# BlueTooth.net
KiCad netlist of a schematic drawn in Altium Designer
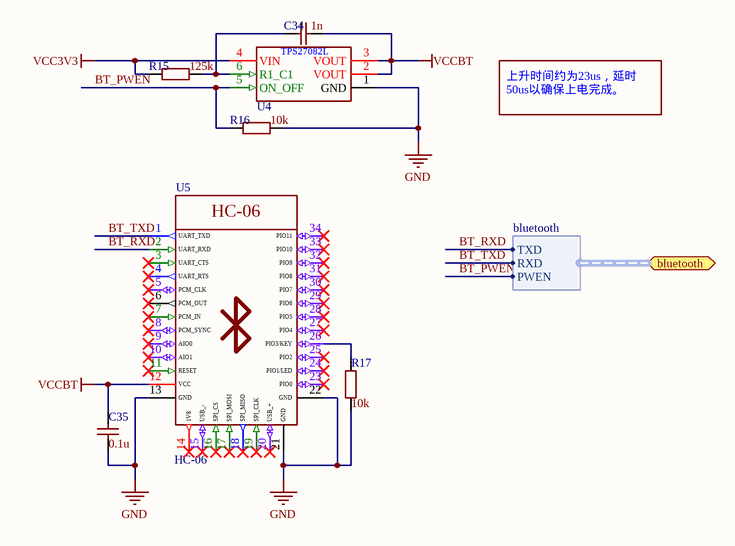
[diagram p0: BlueTooth.SchDoc]

(export (version "E")
  (design (tool "Eeschema 10.0.6"))
  (components
    (comp (ref "C34")
      (value "1n")
      (footprint "C0402_h")
      (description "Capacitor")
      (fields (field (name "PUBLISHER") "Altium Limited"))
      (libsource (lib "电子元件封装库") (part "贴片电容-无极性"))
    )
    (comp (ref "C35")
      (value "0.1u")
      (footprint "C0402_h")
      (description "Capacitor")
      (fields (field (name "PUBLISHER") "Altium Limited"))
      (libsource (lib "电子元件封装库") (part "贴片电容-无极性"))
    )
    (comp (ref "R15")
      (value "125k")
      (footprint "R0402")
      (description "Register")
      (libsource (lib "") (part "贴片电阻_1"))
    )
    (comp (ref "R16")
      (value "10k")
      (footprint "R0402")
      (description "Register")
      (libsource (lib "") (part "贴片电阻_1"))
    )
    (comp (ref "R17")
      (value "10k")
      (footprint "R0402")
      (description "Register")
      (libsource (lib "电子元件封装库") (part "贴片电阻"))
    )
    (comp (ref "U4")
      (value "TPS27082L")
      (footprint "SOT23-6")
      (description "load switch")
      (fields (field (name "PARTNUMBER") "TPS27082LDDC") (field (name "MANUFACTURER") "Texas Instruments"))
      (libsource (lib "电子元件封装库") (part "TPS27082LDDCR"))
    )
    (comp (ref "U5")
      (value "HC-06")
      (footprint "HC-0X-bluetooth")
      (description "HC-06 Bluetooth")
      (libsource (lib "电子元件封装库") (part "HC-06 Bluetooth"))
    )
  )
  (nets
    (net (code "2") (name "/BT_PWEN") (class "Default")
      (node (ref "R16") (pin "1") (pinfunction "1_1") (pintype "passive"))
      (node (ref "U4") (pin "5") (pinfunction "ON_OFF_5") (pintype "input"))
    )
    (net (code "3") (name "/BT_RXD") (class "Default")
      (node (ref "U5") (pin "2") (pinfunction "UART_RXD_2") (pintype "input"))
    )
    (net (code "4") (name "/BT_TXD") (class "Default")
      (node (ref "U5") (pin "1") (pinfunction "UART_TXD_1") (pintype "output"))
    )
    (net (code "6") (name "GND") (class "Default")
      (node (ref "C35") (pin "1") (pinfunction "1_1") (pintype "passive"))
      (node (ref "R16") (pin "2") (pinfunction "2_2") (pintype "passive"))
      (node (ref "R17") (pin "1") (pinfunction "1_1") (pintype "passive"))
      (node (ref "U4") (pin "1") (pinfunction "GND_1") (pintype "power_in"))
      (node (ref "U5") (pin "13") (pinfunction "GND_13") (pintype "power_in"))
      (node (ref "U5") (pin "21") (pinfunction "GND_21") (pintype "power_in"))
      (node (ref "U5") (pin "22") (pinfunction "GND_22") (pintype "power_in"))
    )
    (net (code "7") (name "Net-(U4-R1_C1)") (class "Default")
      (node (ref "C34") (pin "1") (pinfunction "1_1") (pintype "passive"))
      (node (ref "R15") (pin "2") (pinfunction "2_2") (pintype "passive"))
      (node (ref "U4") (pin "6") (pinfunction "R1_C1_6") (pintype "input"))
    )
    (net (code "8") (name "Net-(U5-PIO3{slash}KEY)") (class "Default")
      (node (ref "R17") (pin "2") (pinfunction "2_2") (pintype "passive"))
      (node (ref "U5") (pin "26") (pinfunction "PIO3/KEY_26") (pintype "bidirectional"))
    )
    (net (code "9") (name "VCC3V3") (class "Default")
      (node (ref "R15") (pin "1") (pinfunction "1_1") (pintype "passive"))
      (node (ref "U4") (pin "4") (pinfunction "VIN_4") (pintype "power_in"))
    )
    (net (code "10") (name "VCCBT") (class "Default")
      (node (ref "C34") (pin "2") (pinfunction "2_2") (pintype "passive"))
      (node (ref "C35") (pin "2") (pinfunction "2_2") (pintype "passive"))
      (node (ref "U4") (pin "2") (pinfunction "VOUT_2") (pintype "power_in"))
      (node (ref "U4") (pin "3") (pinfunction "VOUT_3") (pintype "power_in"))
      (node (ref "U5") (pin "12") (pinfunction "VCC_12") (pintype "power_in"))
    )
    (net (code "11") (name "unconnected-(U5-1V8-Pad14)") (class "Default")
      (node (ref "U5") (pin "14") (pinfunction "1V8_14") (pintype "output+no_connect"))
    )
    (net (code "12") (name "unconnected-(U5-AIO0-Pad9)") (class "Default")
      (node (ref "U5") (pin "9") (pinfunction "AIO0_9") (pintype "bidirectional+no_connect"))
    )
    (net (code "13") (name "unconnected-(U5-AIO1-Pad10)") (class "Default")
      (node (ref "U5") (pin "10") (pinfunction "AIO1_10") (pintype "bidirectional+no_connect"))
    )
    (net (code "14") (name "unconnected-(U5-PCM_CLK-Pad5)") (class "Default")
      (node (ref "U5") (pin "5") (pinfunction "PCM_CLK_5") (pintype "bidirectional+no_connect"))
    )
    (net (code "15") (name "unconnected-(U5-PCM_IN-Pad7)") (class "Default")
      (node (ref "U5") (pin "7") (pinfunction "PCM_IN_7") (pintype "input+no_connect"))
    )
    (net (code "16") (name "unconnected-(U5-PCM_OUT-Pad6)") (class "Default")
      (node (ref "U5") (pin "6") (pinfunction "PCM_OUT_6") (pintype "output+no_connect"))
    )
    (net (code "17") (name "unconnected-(U5-PCM_SYNC-Pad8)") (class "Default")
      (node (ref "U5") (pin "8") (pinfunction "PCM_SYNC_8") (pintype "bidirectional+no_connect"))
    )
    (net (code "18") (name "unconnected-(U5-PIO0-Pad23)") (class "Default")
      (node (ref "U5") (pin "23") (pinfunction "PIO0_23") (pintype "bidirectional+no_connect"))
    )
    (net (code "19") (name "unconnected-(U5-PIO1{slash}LED-Pad24)") (class "Default")
      (node (ref "U5") (pin "24") (pinfunction "PIO1/LED_24") (pintype "bidirectional+no_connect"))
    )
    (net (code "20") (name "unconnected-(U5-PIO2-Pad25)") (class "Default")
      (node (ref "U5") (pin "25") (pinfunction "PIO2_25") (pintype "bidirectional+no_connect"))
    )
    (net (code "21") (name "unconnected-(U5-PIO4-Pad27)") (class "Default")
      (node (ref "U5") (pin "27") (pinfunction "PIO4_27") (pintype "bidirectional+no_connect"))
    )
    (net (code "22") (name "unconnected-(U5-PIO5-Pad28)") (class "Default")
      (node (ref "U5") (pin "28") (pinfunction "PIO5_28") (pintype "bidirectional+no_connect"))
    )
    (net (code "23") (name "unconnected-(U5-PIO6-Pad29)") (class "Default")
      (node (ref "U5") (pin "29") (pinfunction "PIO6_29") (pintype "bidirectional+no_connect"))
    )
    (net (code "24") (name "unconnected-(U5-PIO7-Pad30)") (class "Default")
      (node (ref "U5") (pin "30") (pinfunction "PIO7_30") (pintype "bidirectional+no_connect"))
    )
    (net (code "25") (name "unconnected-(U5-PIO8-Pad31)") (class "Default")
      (node (ref "U5") (pin "31") (pinfunction "PIO8_31") (pintype "bidirectional+no_connect"))
    )
    (net (code "26") (name "unconnected-(U5-PIO9-Pad32)") (class "Default")
      (node (ref "U5") (pin "32") (pinfunction "PIO9_32") (pintype "bidirectional+no_connect"))
    )
    (net (code "27") (name "unconnected-(U5-PIO10-Pad33)") (class "Default")
      (node (ref "U5") (pin "33") (pinfunction "PIO10_33") (pintype "bidirectional+no_connect"))
    )
    (net (code "28") (name "unconnected-(U5-PIO11-Pad34)") (class "Default")
      (node (ref "U5") (pin "34") (pinfunction "PIO11_34") (pintype "bidirectional+no_connect"))
    )
    (net (code "29") (name "unconnected-(U5-RESET-Pad11)") (class "Default")
      (node (ref "U5") (pin "11") (pinfunction "RESET_11") (pintype "input+no_connect"))
    )
    (net (code "30") (name "unconnected-(U5-SPI_CLK-Pad19)") (class "Default")
      (node (ref "U5") (pin "19") (pinfunction "SPI_CLK_19") (pintype "input+no_connect"))
    )
    (net (code "31") (name "unconnected-(U5-SPI_CS-Pad16)") (class "Default")
      (node (ref "U5") (pin "16") (pinfunction "SPI_CS_16") (pintype "input+no_connect"))
    )
    (net (code "32") (name "unconnected-(U5-SPI_MISO-Pad18)") (class "Default")
      (node (ref "U5") (pin "18") (pinfunction "SPI_MISO_18") (pintype "output+no_connect"))
    )
    (net (code "33") (name "unconnected-(U5-SPI_MOSI-Pad17)") (class "Default")
      (node (ref "U5") (pin "17") (pinfunction "SPI_MOSI_17") (pintype "input+no_connect"))
    )
    (net (code "34") (name "unconnected-(U5-UART_CTS-Pad3)") (class "Default")
      (node (ref "U5") (pin "3") (pinfunction "UART_CTS_3") (pintype "input+no_connect"))
    )
    (net (code "35") (name "unconnected-(U5-UART_RTS-Pad4)") (class "Default")
      (node (ref "U5") (pin "4") (pinfunction "UART_RTS_4") (pintype "output+no_connect"))
    )
    (net (code "36") (name "unconnected-(U5-USB_+-Pad20)") (class "Default")
      (node (ref "U5") (pin "20") (pinfunction "USB_+_20") (pintype "bidirectional+no_connect"))
    )
    (net (code "37") (name "unconnected-(U5-USB_--Pad15)") (class "Default")
      (node (ref "U5") (pin "15") (pinfunction "USB_-_15") (pintype "bidirectional+no_connect"))
    )
  )
)
